# nm_temp_sens.net
KiCad netlist of a schematic drawn in Altium Designer
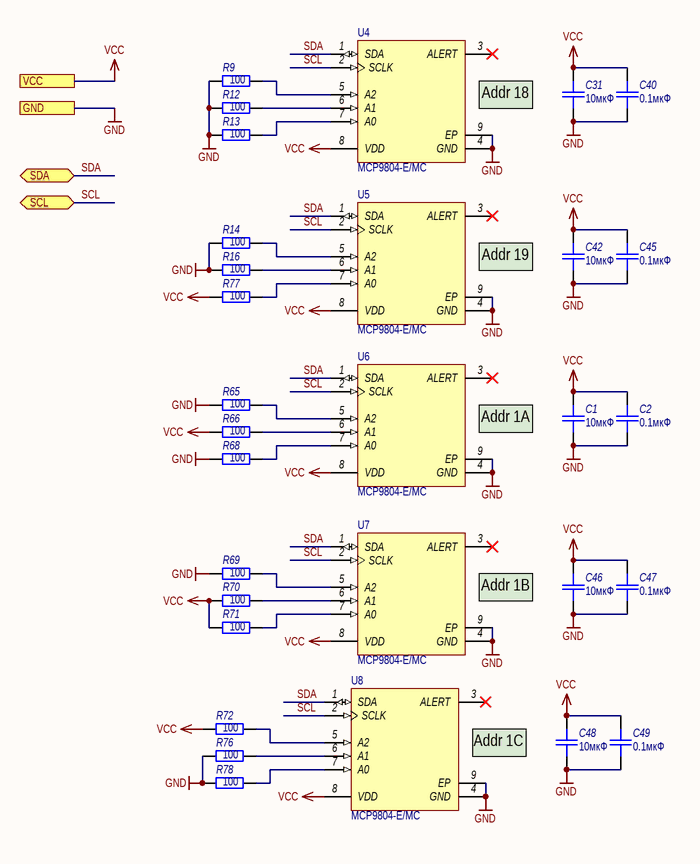
[diagram p0: nm_temp_sens.SchDoc]

(export (version "E")
  (design (tool "Eeschema 10.0.6"))
  (components
    (comp (ref "C1")
      (value "10мкФ")
      (footprint "SMD_C0603")
      (description "Capacitor")
      (libsource (lib "Passive") (part "Capacitor"))
    )
    (comp (ref "C2")
      (value "0.1мкФ")
      (footprint "SMD_C0603")
      (description "Capacitor")
      (libsource (lib "Passive") (part "Capacitor"))
    )
    (comp (ref "C31")
      (value "10мкФ")
      (footprint "SMD_C0603")
      (description "Capacitor")
      (libsource (lib "Passive") (part "Capacitor"))
    )
    (comp (ref "C40")
      (value "0.1мкФ")
      (footprint "SMD_C0603")
      (description "Capacitor")
      (libsource (lib "Passive") (part "Capacitor"))
    )
    (comp (ref "C42")
      (value "10мкФ")
      (footprint "SMD_C0603")
      (description "Capacitor")
      (libsource (lib "Passive") (part "Capacitor"))
    )
    (comp (ref "C45")
      (value "0.1мкФ")
      (footprint "SMD_C0603")
      (description "Capacitor")
      (libsource (lib "Passive") (part "Capacitor"))
    )
    (comp (ref "C46")
      (value "10мкФ")
      (footprint "SMD_C0603")
      (description "Capacitor")
      (libsource (lib "Passive") (part "Capacitor"))
    )
    (comp (ref "C47")
      (value "0.1мкФ")
      (footprint "SMD_C0603")
      (description "Capacitor")
      (libsource (lib "Passive") (part "Capacitor"))
    )
    (comp (ref "C48")
      (value "10мкФ")
      (footprint "SMD_C0603")
      (description "Capacitor")
      (libsource (lib "Passive") (part "Capacitor"))
    )
    (comp (ref "C49")
      (value "0.1мкФ")
      (footprint "SMD_C0603")
      (description "Capacitor")
      (libsource (lib "Passive") (part "Capacitor"))
    )
    (comp (ref "R9")
      (value "100")
      (footprint "SMD_0603")
      (description "Resistor")
      (libsource (lib "Passive") (part "Resistor"))
    )
    (comp (ref "R12")
      (value "100")
      (footprint "SMD_0603")
      (description "Resistor")
      (libsource (lib "Passive") (part "Resistor"))
    )
    (comp (ref "R13")
      (value "100")
      (footprint "SMD_0603")
      (description "Resistor")
      (libsource (lib "Passive") (part "Resistor"))
    )
    (comp (ref "R14")
      (value "100")
      (footprint "SMD_0603")
      (description "Resistor")
      (libsource (lib "Passive") (part "Resistor"))
    )
    (comp (ref "R16")
      (value "100")
      (footprint "SMD_0603")
      (description "Resistor")
      (libsource (lib "Passive") (part "Resistor"))
    )
    (comp (ref "R65")
      (value "100")
      (footprint "SMD_0603")
      (description "Resistor")
      (libsource (lib "Passive") (part "Resistor"))
    )
    (comp (ref "R66")
      (value "100")
      (footprint "SMD_0603")
      (description "Resistor")
      (libsource (lib "Passive") (part "Resistor"))
    )
    (comp (ref "R68")
      (value "100")
      (footprint "SMD_0603")
      (description "Resistor")
      (libsource (lib "Passive") (part "Resistor"))
    )
    (comp (ref "R69")
      (value "100")
      (footprint "SMD_0603")
      (description "Resistor")
      (libsource (lib "Passive") (part "Resistor"))
    )
    (comp (ref "R70")
      (value "100")
      (footprint "SMD_0603")
      (description "Resistor")
      (libsource (lib "Passive") (part "Resistor"))
    )
    (comp (ref "R71")
      (value "100")
      (footprint "SMD_0603")
      (description "Resistor")
      (libsource (lib "Passive") (part "Resistor"))
    )
    (comp (ref "R72")
      (value "100")
      (footprint "SMD_0603")
      (description "Resistor")
      (libsource (lib "Passive") (part "Resistor"))
    )
    (comp (ref "R76")
      (value "100")
      (footprint "SMD_0603")
      (description "Resistor")
      (libsource (lib "Passive") (part "Resistor"))
    )
    (comp (ref "R77")
      (value "100")
      (footprint "SMD_0603")
      (description "Resistor")
      (libsource (lib "Passive") (part "Resistor"))
    )
    (comp (ref "R78")
      (value "100")
      (footprint "SMD_0603")
      (description "Resistor")
      (libsource (lib "Passive") (part "Resistor"))
    )
    (comp (ref "U4")
      (value "MCP9804-E/MC")
      (footprint "DFN-MC8")
      (description "±0.25°C Typ. Accuracy Digital Temperature Sensor, 8-Pin DFN, Extended Temperature")
      (libsource (lib "MCP9804") (part "CMP-0192-00111-1"))
    )
    (comp (ref "U5")
      (value "MCP9804-E/MC")
      (footprint "DFN-MC8")
      (description "±0.25°C Typ. Accuracy Digital Temperature Sensor, 8-Pin DFN, Extended Temperature")
      (libsource (lib "MCP9804") (part "CMP-0192-00111-1"))
    )
    (comp (ref "U6")
      (value "MCP9804-E/MC")
      (footprint "DFN-MC8")
      (description "±0.25°C Typ. Accuracy Digital Temperature Sensor, 8-Pin DFN, Extended Temperature")
      (libsource (lib "MCP9804") (part "CMP-0192-00111-1"))
    )
    (comp (ref "U7")
      (value "MCP9804-E/MC")
      (footprint "DFN-MC8")
      (description "±0.25°C Typ. Accuracy Digital Temperature Sensor, 8-Pin DFN, Extended Temperature")
      (libsource (lib "MCP9804") (part "CMP-0192-00111-1"))
    )
    (comp (ref "U8")
      (value "MCP9804-E/MC")
      (footprint "DFN-MC8")
      (description "±0.25°C Typ. Accuracy Digital Temperature Sensor, 8-Pin DFN, Extended Temperature")
      (libsource (lib "MCP9804") (part "CMP-0192-00111-1"))
    )
  )
  (nets
    (net (code "1") (name "/SCL") (class "Default")
      (node (ref "U4") (pin "2") (pinfunction "SCLK_2") (pintype "input"))
      (node (ref "U5") (pin "2") (pinfunction "SCLK_2") (pintype "input"))
      (node (ref "U6") (pin "2") (pinfunction "SCLK_2") (pintype "input"))
      (node (ref "U7") (pin "2") (pinfunction "SCLK_2") (pintype "input"))
      (node (ref "U8") (pin "2") (pinfunction "SCLK_2") (pintype "input"))
    )
    (net (code "2") (name "/SDA") (class "Default")
      (node (ref "U4") (pin "1") (pinfunction "SDA_1") (pintype "bidirectional"))
      (node (ref "U5") (pin "1") (pinfunction "SDA_1") (pintype "bidirectional"))
      (node (ref "U6") (pin "1") (pinfunction "SDA_1") (pintype "bidirectional"))
      (node (ref "U7") (pin "1") (pinfunction "SDA_1") (pintype "bidirectional"))
      (node (ref "U8") (pin "1") (pinfunction "SDA_1") (pintype "bidirectional"))
    )
    (net (code "3") (name "GND") (class "Default")
      (node (ref "C1") (pin "1") (pinfunction "1_1") (pintype "passive"))
      (node (ref "C2") (pin "1") (pinfunction "1_1") (pintype "passive"))
      (node (ref "C31") (pin "1") (pinfunction "1_1") (pintype "passive"))
      (node (ref "C40") (pin "1") (pinfunction "1_1") (pintype "passive"))
      (node (ref "C42") (pin "1") (pinfunction "1_1") (pintype "passive"))
      (node (ref "C45") (pin "1") (pinfunction "1_1") (pintype "passive"))
      (node (ref "C46") (pin "1") (pinfunction "1_1") (pintype "passive"))
      (node (ref "C47") (pin "1") (pinfunction "1_1") (pintype "passive"))
      (node (ref "C48") (pin "1") (pinfunction "1_1") (pintype "passive"))
      (node (ref "C49") (pin "1") (pinfunction "1_1") (pintype "passive"))
      (node (ref "R12") (pin "1") (pinfunction "1_1") (pintype "passive"))
      (node (ref "R13") (pin "1") (pinfunction "1_1") (pintype "passive"))
      (node (ref "R14") (pin "1") (pinfunction "1_1") (pintype "passive"))
      (node (ref "R16") (pin "1") (pinfunction "1_1") (pintype "passive"))
      (node (ref "R65") (pin "1") (pinfunction "1_1") (pintype "passive"))
      (node (ref "R68") (pin "1") (pinfunction "1_1") (pintype "passive"))
      (node (ref "R69") (pin "1") (pinfunction "1_1") (pintype "passive"))
      (node (ref "R76") (pin "1") (pinfunction "1_1") (pintype "passive"))
      (node (ref "R78") (pin "1") (pinfunction "1_1") (pintype "passive"))
      (node (ref "R9") (pin "1") (pinfunction "1_1") (pintype "passive"))
      (node (ref "U4") (pin "4") (pinfunction "GND_4") (pintype "power_in"))
      (node (ref "U4") (pin "9") (pinfunction "EP_9") (pintype "passive"))
      (node (ref "U5") (pin "4") (pinfunction "GND_4") (pintype "power_in"))
      (node (ref "U5") (pin "9") (pinfunction "EP_9") (pintype "passive"))
      (node (ref "U6") (pin "4") (pinfunction "GND_4") (pintype "power_in"))
      (node (ref "U6") (pin "9") (pinfunction "EP_9") (pintype "passive"))
      (node (ref "U7") (pin "4") (pinfunction "GND_4") (pintype "power_in"))
      (node (ref "U7") (pin "9") (pinfunction "EP_9") (pintype "passive"))
      (node (ref "U8") (pin "4") (pinfunction "GND_4") (pintype "power_in"))
      (node (ref "U8") (pin "9") (pinfunction "EP_9") (pintype "passive"))
    )
    (net (code "4") (name "Net-(U4-A0)") (class "Default")
      (node (ref "R13") (pin "2") (pinfunction "2_2") (pintype "passive"))
      (node (ref "U4") (pin "7") (pinfunction "A0_7") (pintype "input"))
    )
    (net (code "5") (name "Net-(U4-A1)") (class "Default")
      (node (ref "R12") (pin "2") (pinfunction "2_2") (pintype "passive"))
      (node (ref "U4") (pin "6") (pinfunction "A1_6") (pintype "input"))
    )
    (net (code "6") (name "Net-(U4-A2)") (class "Default")
      (node (ref "R9") (pin "2") (pinfunction "2_2") (pintype "passive"))
      (node (ref "U4") (pin "5") (pinfunction "A2_5") (pintype "input"))
    )
    (net (code "7") (name "Net-(U5-A0)") (class "Default")
      (node (ref "R77") (pin "2") (pinfunction "2_2") (pintype "passive"))
      (node (ref "U5") (pin "7") (pinfunction "A0_7") (pintype "input"))
    )
    (net (code "8") (name "Net-(U5-A1)") (class "Default")
      (node (ref "R16") (pin "2") (pinfunction "2_2") (pintype "passive"))
      (node (ref "U5") (pin "6") (pinfunction "A1_6") (pintype "input"))
    )
    (net (code "9") (name "Net-(U5-A2)") (class "Default")
      (node (ref "R14") (pin "2") (pinfunction "2_2") (pintype "passive"))
      (node (ref "U5") (pin "5") (pinfunction "A2_5") (pintype "input"))
    )
    (net (code "10") (name "Net-(U6-A0)") (class "Default")
      (node (ref "R68") (pin "2") (pinfunction "2_2") (pintype "passive"))
      (node (ref "U6") (pin "7") (pinfunction "A0_7") (pintype "input"))
    )
    (net (code "11") (name "Net-(U6-A1)") (class "Default")
      (node (ref "R66") (pin "2") (pinfunction "2_2") (pintype "passive"))
      (node (ref "U6") (pin "6") (pinfunction "A1_6") (pintype "input"))
    )
    (net (code "12") (name "Net-(U6-A2)") (class "Default")
      (node (ref "R65") (pin "2") (pinfunction "2_2") (pintype "passive"))
      (node (ref "U6") (pin "5") (pinfunction "A2_5") (pintype "input"))
    )
    (net (code "13") (name "Net-(U7-A0)") (class "Default")
      (node (ref "R71") (pin "2") (pinfunction "2_2") (pintype "passive"))
      (node (ref "U7") (pin "7") (pinfunction "A0_7") (pintype "input"))
    )
    (net (code "14") (name "Net-(U7-A1)") (class "Default")
      (node (ref "R70") (pin "2") (pinfunction "2_2") (pintype "passive"))
      (node (ref "U7") (pin "6") (pinfunction "A1_6") (pintype "input"))
    )
    (net (code "15") (name "Net-(U7-A2)") (class "Default")
      (node (ref "R69") (pin "2") (pinfunction "2_2") (pintype "passive"))
      (node (ref "U7") (pin "5") (pinfunction "A2_5") (pintype "input"))
    )
    (net (code "16") (name "Net-(U8-A0)") (class "Default")
      (node (ref "R78") (pin "2") (pinfunction "2_2") (pintype "passive"))
      (node (ref "U8") (pin "7") (pinfunction "A0_7") (pintype "input"))
    )
    (net (code "17") (name "Net-(U8-A1)") (class "Default")
      (node (ref "R76") (pin "2") (pinfunction "2_2") (pintype "passive"))
      (node (ref "U8") (pin "6") (pinfunction "A1_6") (pintype "input"))
    )
    (net (code "18") (name "Net-(U8-A2)") (class "Default")
      (node (ref "R72") (pin "2") (pinfunction "2_2") (pintype "passive"))
      (node (ref "U8") (pin "5") (pinfunction "A2_5") (pintype "input"))
    )
    (net (code "19") (name "VCC") (class "Default")
      (node (ref "C1") (pin "2") (pinfunction "2_2") (pintype "passive"))
      (node (ref "C2") (pin "2") (pinfunction "2_2") (pintype "passive"))
      (node (ref "C31") (pin "2") (pinfunction "2_2") (pintype "passive"))
      (node (ref "C40") (pin "2") (pinfunction "2_2") (pintype "passive"))
      (node (ref "C42") (pin "2") (pinfunction "2_2") (pintype "passive"))
      (node (ref "C45") (pin "2") (pinfunction "2_2") (pintype "passive"))
      (node (ref "C46") (pin "2") (pinfunction "2_2") (pintype "passive"))
      (node (ref "C47") (pin "2") (pinfunction "2_2") (pintype "passive"))
      (node (ref "C48") (pin "2") (pinfunction "2_2") (pintype "passive"))
      (node (ref "C49") (pin "2") (pinfunction "2_2") (pintype "passive"))
      (node (ref "R66") (pin "1") (pinfunction "1_1") (pintype "passive"))
      (node (ref "R70") (pin "1") (pinfunction "1_1") (pintype "passive"))
      (node (ref "R71") (pin "1") (pinfunction "1_1") (pintype "passive"))
      (node (ref "R72") (pin "1") (pinfunction "1_1") (pintype "passive"))
      (node (ref "R77") (pin "1") (pinfunction "1_1") (pintype "passive"))
      (node (ref "U4") (pin "8") (pinfunction "VDD_8") (pintype "power_in"))
      (node (ref "U5") (pin "8") (pinfunction "VDD_8") (pintype "power_in"))
      (node (ref "U6") (pin "8") (pinfunction "VDD_8") (pintype "power_in"))
      (node (ref "U7") (pin "8") (pinfunction "VDD_8") (pintype "power_in"))
      (node (ref "U8") (pin "8") (pinfunction "VDD_8") (pintype "power_in"))
    )
    (net (code "20") (name "unconnected-(U4-ALERT-Pad3)") (class "Default")
      (node (ref "U4") (pin "3") (pinfunction "ALERT_3") (pintype "open_collector+no_connect"))
    )
    (net (code "21") (name "unconnected-(U5-ALERT-Pad3)") (class "Default")
      (node (ref "U5") (pin "3") (pinfunction "ALERT_3") (pintype "open_collector+no_connect"))
    )
    (net (code "22") (name "unconnected-(U6-ALERT-Pad3)") (class "Default")
      (node (ref "U6") (pin "3") (pinfunction "ALERT_3") (pintype "open_collector+no_connect"))
    )
    (net (code "23") (name "unconnected-(U7-ALERT-Pad3)") (class "Default")
      (node (ref "U7") (pin "3") (pinfunction "ALERT_3") (pintype "open_collector+no_connect"))
    )
    (net (code "24") (name "unconnected-(U8-ALERT-Pad3)") (class "Default")
      (node (ref "U8") (pin "3") (pinfunction "ALERT_3") (pintype "open_collector+no_connect"))
    )
  )
)
